# guac_v2.net
KiCad netlist of a schematic drawn in EAGLE
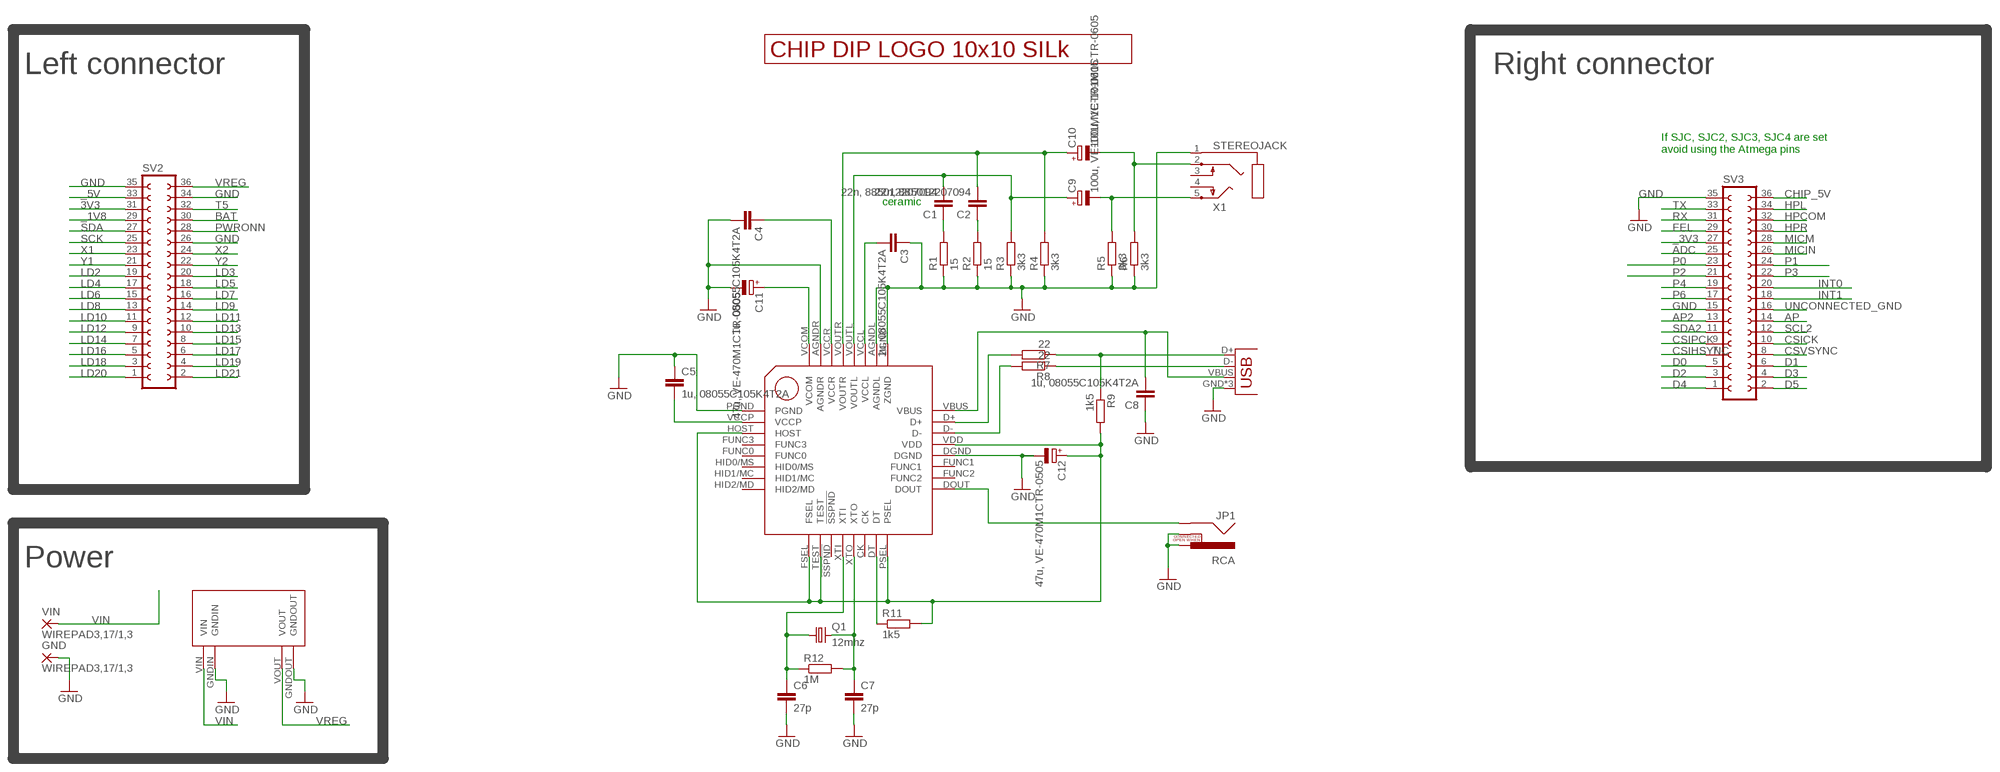
[diagram p0: schematic, sheet 1]

(export (version "E")
  (design (tool "Eeschema 10.0.6"))
  (components
    (comp (ref "C1")
      (value "22n, 885012207094")
      (footprint "eagle-import:C0805")
      (libsource (lib "eagle-import") (part "C-EUC0805"))
    )
    (comp (ref "C2")
      (value "22n, 885012207094")
      (footprint "eagle-import:C0805")
      (libsource (lib "eagle-import") (part "C-EUC0805"))
    )
    (comp (ref "C3")
      (value "1u, 08055C105K4T2A")
      (footprint "eagle-import:C0805")
      (libsource (lib "eagle-import") (part "C-EUC0805"))
    )
    (comp (ref "C4")
      (value "1u, 08055C105K4T2A")
      (footprint "eagle-import:C0805")
      (libsource (lib "eagle-import") (part "C-EUC0805"))
    )
    (comp (ref "C5")
      (value "1u, 08055C105K4T2A")
      (footprint "eagle-import:C0805")
      (libsource (lib "eagle-import") (part "C-EUC0805"))
    )
    (comp (ref "C6")
      (value "27p")
      (footprint "eagle-import:C0805")
      (libsource (lib "eagle-import") (part "C-EUC0805"))
    )
    (comp (ref "C7")
      (value "27p")
      (footprint "eagle-import:C0805")
      (libsource (lib "eagle-import") (part "C-EUC0805"))
    )
    (comp (ref "C8")
      (value "1u, 08055C105K4T2A")
      (footprint "eagle-import:C0805")
      (libsource (lib "eagle-import") (part "C-EUC0805"))
    )
    (comp (ref "C9")
      (value "100u, VE-101M1CTR-0605")
      (footprint "eagle-import:140CLH-0810")
      (libsource (lib "eagle-import") (part "CPOL-EU140CLH-0810"))
    )
    (comp (ref "C10")
      (value "100u, VE-101M1CTR-0605")
      (footprint "eagle-import:140CLH-0810")
      (libsource (lib "eagle-import") (part "CPOL-EU140CLH-0810"))
    )
    (comp (ref "C11")
      (value "47u, VE-470M1CTR-0505")
      (footprint "eagle-import:140CLH-0810")
      (libsource (lib "eagle-import") (part "CPOL-EU140CLH-0810"))
    )
    (comp (ref "C12")
      (value "47u, VE-470M1CTR-0505")
      (footprint "eagle-import:140CLH-0810")
      (libsource (lib "eagle-import") (part "CPOL-EU140CLH-0810"))
    )
    (comp (ref "GND")
      (value "WIREPAD3,17/1,3")
      (footprint "eagle-import:3,17_1,3")
      (libsource (lib "eagle-import") (part "WIREPAD3,17/1,3"))
    )
    (comp (ref "JP1")
      (value "RCA")
      (footprint "eagle-import:RCA")
      (libsource (lib "eagle-import") (part "RCA"))
    )
    (comp (ref "Q1")
      (value "12mhz")
      (footprint "eagle-import:HC49UP")
      (libsource (lib "eagle-import") (part "CRYSTALHC49UP"))
    )
    (comp (ref "R1")
      (value "15")
      (footprint "eagle-import:M0805")
      (libsource (lib "eagle-import") (part "R-EU_M0805"))
    )
    (comp (ref "R2")
      (value "15")
      (footprint "eagle-import:M0805")
      (libsource (lib "eagle-import") (part "R-EU_M0805"))
    )
    (comp (ref "R3")
      (value "3k3")
      (footprint "eagle-import:M0805")
      (libsource (lib "eagle-import") (part "R-EU_M0805"))
    )
    (comp (ref "R4")
      (value "3k3")
      (footprint "eagle-import:M0805")
      (libsource (lib "eagle-import") (part "R-EU_M0805"))
    )
    (comp (ref "R5")
      (value "3k3")
      (footprint "eagle-import:M0805")
      (libsource (lib "eagle-import") (part "R-EU_M0805"))
    )
    (comp (ref "R6")
      (value "3k3")
      (footprint "eagle-import:M0805")
      (libsource (lib "eagle-import") (part "R-EU_M0805"))
    )
    (comp (ref "R7")
      (value "22")
      (footprint "eagle-import:M0805")
      (libsource (lib "eagle-import") (part "R-EU_M0805"))
    )
    (comp (ref "R8")
      (value "22")
      (footprint "eagle-import:M0805")
      (libsource (lib "eagle-import") (part "R-EU_M0805"))
    )
    (comp (ref "R9")
      (value "1k5")
      (footprint "eagle-import:M0805")
      (libsource (lib "eagle-import") (part "R-EU_M0805"))
    )
    (comp (ref "R11")
      (value "1k5")
      (footprint "eagle-import:M0805")
      (libsource (lib "eagle-import") (part "R-EU_M0805"))
    )
    (comp (ref "R12")
      (value "1M")
      (footprint "eagle-import:M0805")
      (libsource (lib "eagle-import") (part "R-EU_M0805"))
    )
    (comp (ref "SV2")
      (value "FE18-2")
      (footprint "eagle-import:FE18-2")
      (libsource (lib "eagle-import") (part "FE18-2"))
    )
    (comp (ref "SV3")
      (value "FE18-2")
      (footprint "eagle-import:FE18-2")
      (libsource (lib "eagle-import") (part "FE18-2"))
    )
    (comp (ref "U$1")
      (value "PCM2706")
      (footprint "eagle-import:TQFP32-08")
      (libsource (lib "eagle-import") (part "PCM2706"))
    )
    (comp (ref "U$3")
      (value "LOGO_10X10_SILK")
      (footprint "eagle-import:LOGO_10X10_SILK")
      (libsource (lib "eagle-import") (part "LOGO_10X10_SILK"))
    )
    (comp (ref "U$9")
      (value "MP1584EN_FRAMELESS")
      (footprint "eagle-import:MP1584EN_FRAMELESS")
      (libsource (lib "eagle-import") (part "MP1584EN_FRAMELESS"))
    )
    (comp (ref "USB")
      (value "USBUSB-MICROB-SMT-DIP")
      (footprint "eagle-import:USB-MICROB-SMT-DIP")
      (libsource (lib "eagle-import") (part "USBUSB-MICROB-SMT-DIP"))
    )
    (comp (ref "VIN")
      (value "WIREPAD3,17/1,3")
      (footprint "eagle-import:3,17_1,3")
      (libsource (lib "eagle-import") (part "WIREPAD3,17/1,3"))
    )
    (comp (ref "X1")
      (value "STEREOJACK")
      (footprint "eagle-import:STX3100")
      (libsource (lib "eagle-import") (part "STEREOJACK"))
    )
  )
  (nets
    (net (code "1") (name "/3V3") (class "Default")
      (node (ref "SV2") (pin "31") (pinfunction "31_31") (pintype "passive"))
    )
    (net (code "2") (name "/ADC") (class "Default")
      (node (ref "SV3") (pin "25") (pinfunction "25_25") (pintype "passive"))
    )
    (net (code "3") (name "/AP") (class "Default")
      (node (ref "SV3") (pin "14") (pinfunction "14_14") (pintype "passive"))
    )
    (net (code "4") (name "/AP2") (class "Default")
      (node (ref "SV3") (pin "13") (pinfunction "13_13") (pintype "passive"))
    )
    (net (code "5") (name "/BAT") (class "Default")
      (node (ref "SV2") (pin "30") (pinfunction "30_30") (pintype "passive"))
    )
    (net (code "6") (name "/CHIP_5V") (class "Default")
      (node (ref "SV3") (pin "36") (pinfunction "36_36") (pintype "passive"))
    )
    (net (code "7") (name "/CSICK") (class "Default")
      (node (ref "SV3") (pin "10") (pinfunction "10_10") (pintype "passive"))
    )
    (net (code "8") (name "/CSIHSYNC") (class "Default")
      (node (ref "SV3") (pin "7") (pinfunction "7_7") (pintype "passive"))
    )
    (net (code "9") (name "/CSIPCK") (class "Default")
      (node (ref "SV3") (pin "9") (pinfunction "9_9") (pintype "passive"))
    )
    (net (code "10") (name "/CSVSYNC") (class "Default")
      (node (ref "SV3") (pin "8") (pinfunction "8_8") (pintype "passive"))
    )
    (net (code "11") (name "/D0") (class "Default")
      (node (ref "SV3") (pin "5") (pinfunction "5_5") (pintype "passive"))
    )
    (net (code "12") (name "/D1") (class "Default")
      (node (ref "SV3") (pin "6") (pinfunction "6_6") (pintype "passive"))
    )
    (net (code "13") (name "/D2") (class "Default")
      (node (ref "SV3") (pin "3") (pinfunction "3_3") (pintype "passive"))
    )
    (net (code "14") (name "/D3") (class "Default")
      (node (ref "SV3") (pin "4") (pinfunction "4_4") (pintype "passive"))
    )
    (net (code "15") (name "/D4") (class "Default")
      (node (ref "SV3") (pin "1") (pinfunction "1_1") (pintype "passive"))
    )
    (net (code "16") (name "/D5") (class "Default")
      (node (ref "SV3") (pin "2") (pinfunction "2_2") (pintype "passive"))
    )
    (net (code "17") (name "/FEL") (class "Default")
      (node (ref "SV3") (pin "29") (pinfunction "29_29") (pintype "passive"))
    )
    (net (code "18") (name "/HPCOM") (class "Default")
      (node (ref "SV3") (pin "32") (pinfunction "32_32") (pintype "passive"))
    )
    (net (code "19") (name "/HPL") (class "Default")
      (node (ref "SV3") (pin "34") (pinfunction "34_34") (pintype "passive"))
    )
    (net (code "20") (name "/HPR") (class "Default")
      (node (ref "SV3") (pin "30") (pinfunction "30_30") (pintype "passive"))
    )
    (net (code "21") (name "/INT0") (class "Default")
      (node (ref "SV3") (pin "20") (pinfunction "20_20") (pintype "passive"))
    )
    (net (code "22") (name "/INT1") (class "Default")
      (node (ref "SV3") (pin "18") (pinfunction "18_18") (pintype "passive"))
    )
    (net (code "23") (name "/LD2") (class "Default")
      (node (ref "SV2") (pin "19") (pinfunction "19_19") (pintype "passive"))
    )
    (net (code "24") (name "/LD3") (class "Default")
      (node (ref "SV2") (pin "20") (pinfunction "20_20") (pintype "passive"))
    )
    (net (code "25") (name "/LD4") (class "Default")
      (node (ref "SV2") (pin "17") (pinfunction "17_17") (pintype "passive"))
    )
    (net (code "26") (name "/LD5") (class "Default")
      (node (ref "SV2") (pin "18") (pinfunction "18_18") (pintype "passive"))
    )
    (net (code "27") (name "/LD6") (class "Default")
      (node (ref "SV2") (pin "15") (pinfunction "15_15") (pintype "passive"))
    )
    (net (code "28") (name "/LD7") (class "Default")
      (node (ref "SV2") (pin "16") (pinfunction "16_16") (pintype "passive"))
    )
    (net (code "29") (name "/LD8") (class "Default")
      (node (ref "SV2") (pin "13") (pinfunction "13_13") (pintype "passive"))
    )
    (net (code "30") (name "/LD9") (class "Default")
      (node (ref "SV2") (pin "14") (pinfunction "14_14") (pintype "passive"))
    )
    (net (code "31") (name "/LD10") (class "Default")
      (node (ref "SV2") (pin "11") (pinfunction "11_11") (pintype "passive"))
    )
    (net (code "32") (name "/LD11") (class "Default")
      (node (ref "SV2") (pin "12") (pinfunction "12_12") (pintype "passive"))
    )
    (net (code "33") (name "/LD12") (class "Default")
      (node (ref "SV2") (pin "9") (pinfunction "9_9") (pintype "passive"))
    )
    (net (code "34") (name "/LD13") (class "Default")
      (node (ref "SV2") (pin "10") (pinfunction "10_10") (pintype "passive"))
    )
    (net (code "35") (name "/LD14") (class "Default")
      (node (ref "SV2") (pin "7") (pinfunction "7_7") (pintype "passive"))
    )
    (net (code "36") (name "/LD15") (class "Default")
      (node (ref "SV2") (pin "8") (pinfunction "8_8") (pintype "passive"))
    )
    (net (code "37") (name "/LD16") (class "Default")
      (node (ref "SV2") (pin "5") (pinfunction "5_5") (pintype "passive"))
    )
    (net (code "38") (name "/LD17") (class "Default")
      (node (ref "SV2") (pin "6") (pinfunction "6_6") (pintype "passive"))
    )
    (net (code "39") (name "/LD18") (class "Default")
      (node (ref "SV2") (pin "3") (pinfunction "3_3") (pintype "passive"))
    )
    (net (code "40") (name "/LD19") (class "Default")
      (node (ref "SV2") (pin "4") (pinfunction "4_4") (pintype "passive"))
    )
    (net (code "41") (name "/LD20") (class "Default")
      (node (ref "SV2") (pin "1") (pinfunction "1_1") (pintype "passive"))
    )
    (net (code "42") (name "/LD21") (class "Default")
      (node (ref "SV2") (pin "2") (pinfunction "2_2") (pintype "passive"))
    )
    (net (code "43") (name "/MICIN") (class "Default")
      (node (ref "SV3") (pin "26") (pinfunction "26_26") (pintype "passive"))
    )
    (net (code "44") (name "/MICM") (class "Default")
      (node (ref "SV3") (pin "28") (pinfunction "28_28") (pintype "passive"))
    )
    (net (code "45") (name "/P0") (class "Default")
      (node (ref "SV3") (pin "23") (pinfunction "23_23") (pintype "passive"))
    )
    (net (code "46") (name "/P1") (class "Default")
      (node (ref "SV3") (pin "24") (pinfunction "24_24") (pintype "passive"))
    )
    (net (code "47") (name "/P2") (class "Default")
      (node (ref "SV3") (pin "21") (pinfunction "21_21") (pintype "passive"))
    )
    (net (code "48") (name "/P3") (class "Default")
      (node (ref "SV3") (pin "22") (pinfunction "22_22") (pintype "passive"))
    )
    (net (code "49") (name "/P4") (class "Default")
      (node (ref "SV3") (pin "19") (pinfunction "19_19") (pintype "passive"))
    )
    (net (code "50") (name "/P6") (class "Default")
      (node (ref "SV3") (pin "17") (pinfunction "17_17") (pintype "passive"))
    )
    (net (code "51") (name "/PWRONN") (class "Default")
      (node (ref "SV2") (pin "28") (pinfunction "28_28") (pintype "passive"))
    )
    (net (code "52") (name "/RX") (class "Default")
      (node (ref "SV3") (pin "31") (pinfunction "31_31") (pintype "passive"))
    )
    (net (code "53") (name "/SCK") (class "Default")
      (node (ref "SV2") (pin "25") (pinfunction "25_25") (pintype "passive"))
    )
    (net (code "54") (name "/SCL2") (class "Default")
      (node (ref "SV3") (pin "12") (pinfunction "12_12") (pintype "passive"))
    )
    (net (code "55") (name "/SDA") (class "Default")
      (node (ref "SV2") (pin "27") (pinfunction "27_27") (pintype "passive"))
    )
    (net (code "56") (name "/SDA2") (class "Default")
      (node (ref "SV3") (pin "11") (pinfunction "11_11") (pintype "passive"))
    )
    (net (code "57") (name "/T5") (class "Default")
      (node (ref "SV2") (pin "32") (pinfunction "32_32") (pintype "passive"))
    )
    (net (code "58") (name "/TX") (class "Default")
      (node (ref "SV3") (pin "33") (pinfunction "33_33") (pintype "passive"))
    )
    (net (code "59") (name "/UNCONNECTED_GND") (class "Default")
      (node (ref "SV3") (pin "16") (pinfunction "16_16") (pintype "passive"))
    )
    (net (code "60") (name "/VIN") (class "Default")
      (node (ref "U$9") (pin "VIN") (pinfunction "VIN_VIN") (pintype "power_in"))
      (node (ref "VIN") (pin "1") (pinfunction "P_1") (pintype "passive"))
    )
    (net (code "61") (name "/VREG") (class "Default")
      (node (ref "SV2") (pin "36") (pinfunction "36_36") (pintype "passive"))
      (node (ref "U$9") (pin "VOUT") (pinfunction "VOUT_VOUT") (pintype "power_in"))
    )
    (net (code "62") (name "/X1") (class "Default")
      (node (ref "SV2") (pin "23") (pinfunction "23_23") (pintype "passive"))
    )
    (net (code "63") (name "/X2") (class "Default")
      (node (ref "SV2") (pin "24") (pinfunction "24_24") (pintype "passive"))
    )
    (net (code "64") (name "/Y1") (class "Default")
      (node (ref "SV2") (pin "21") (pinfunction "21_21") (pintype "passive"))
    )
    (net (code "65") (name "/Y2") (class "Default")
      (node (ref "SV2") (pin "22") (pinfunction "22_22") (pintype "passive"))
    )
    (net (code "66") (name "/_1V8") (class "Default")
      (node (ref "SV2") (pin "29") (pinfunction "29_29") (pintype "passive"))
    )
    (net (code "67") (name "/_3V3") (class "Default")
      (node (ref "SV3") (pin "27") (pinfunction "27_27") (pintype "passive"))
    )
    (net (code "68") (name "/_5V") (class "Default")
      (node (ref "SV2") (pin "33") (pinfunction "33_33") (pintype "passive"))
    )
    (net (code "69") (name "GND") (class "Default")
      (node (ref "C11") (pin "-") (pinfunction "-_-") (pintype "passive"))
      (node (ref "C12") (pin "-") (pinfunction "-_-") (pintype "passive"))
      (node (ref "C3") (pin "1") (pinfunction "1_1") (pintype "passive"))
      (node (ref "C4") (pin "2") (pinfunction "2_2") (pintype "passive"))
      (node (ref "C5") (pin "1") (pinfunction "1_1") (pintype "passive"))
      (node (ref "C6") (pin "2") (pinfunction "2_2") (pintype "passive"))
      (node (ref "C7") (pin "2") (pinfunction "2_2") (pintype "passive"))
      (node (ref "C8") (pin "1") (pinfunction "1_1") (pintype "passive"))
      (node (ref "GND") (pin "1") (pinfunction "P_1") (pintype "passive"))
      (node (ref "JP1") (pin "PIN") (pinfunction "PIN_PIN") (pintype "bidirectional"))
      (node (ref "JP1") (pin "SWITCH") (pinfunction "SWITCH_SWITCH") (pintype "bidirectional"))
      (node (ref "R1") (pin "1") (pinfunction "1_1") (pintype "passive"))
      (node (ref "R2") (pin "1") (pinfunction "1_1") (pintype "passive"))
      (node (ref "R3") (pin "1") (pinfunction "1_1") (pintype "passive"))
      (node (ref "R4") (pin "1") (pinfunction "1_1") (pintype "passive"))
      (node (ref "R5") (pin "1") (pinfunction "1_1") (pintype "passive"))
      (node (ref "R6") (pin "1") (pinfunction "1_1") (pintype "passive"))
      (node (ref "SV2") (pin "26") (pinfunction "26_26") (pintype "passive"))
      (node (ref "SV2") (pin "34") (pinfunction "34_34") (pintype "passive"))
      (node (ref "SV2") (pin "35") (pinfunction "35_35") (pintype "passive"))
      (node (ref "SV3") (pin "15") (pinfunction "15_15") (pintype "passive"))
      (node (ref "SV3") (pin "35") (pinfunction "35_35") (pintype "passive"))
      (node (ref "U$1") (pin "AGNDL") (pinfunction "AGNDL_AGNDL") (pintype "power_in"))
      (node (ref "U$1") (pin "AGNDR") (pinfunction "AGNDR_AGNDR") (pintype "power_in"))
      (node (ref "U$1") (pin "DGND") (pinfunction "DGND_DGND") (pintype "power_in"))
      (node (ref "U$1") (pin "PGND") (pinfunction "PGND_PGND") (pintype "power_in"))
      (node (ref "U$1") (pin "ZGND") (pinfunction "ZGND_ZGND") (pintype "power_in"))
      (node (ref "U$9") (pin "GNDIN") (pinfunction "GNDIN_GNDIN") (pintype "power_in"))
      (node (ref "U$9") (pin "GNDOUT") (pinfunction "GNDOUT_GNDOUT") (pintype "power_in"))
      (node (ref "USB") (pin "GND") (pinfunction "GND_GND") (pintype "bidirectional"))
      (node (ref "USB") (pin "MT1") (pinfunction "GND_MT1") (pintype "bidirectional"))
      (node (ref "USB") (pin "MT2") (pinfunction "GND_MT2") (pintype "bidirectional"))
      (node (ref "X1") (pin "1") (pinfunction "1_1") (pintype "passive"))
    )
    (net (code "70") (name "Net-(C1-Pad1)") (class "Default")
      (node (ref "C1") (pin "1") (pinfunction "1_1") (pintype "passive"))
      (node (ref "R1") (pin "2") (pinfunction "2_2") (pintype "passive"))
    )
    (net (code "71") (name "Net-(C1-Pad2)") (class "Default")
      (node (ref "C1") (pin "2") (pinfunction "2_2") (pintype "passive"))
      (node (ref "C9") (pin "+") (pinfunction "+_+") (pintype "passive"))
      (node (ref "R3") (pin "2") (pinfunction "2_2") (pintype "passive"))
      (node (ref "U$1") (pin "VOUTL") (pinfunction "VOUTL_VOUTL") (pintype "output"))
    )
    (net (code "72") (name "Net-(C2-Pad1)") (class "Default")
      (node (ref "C2") (pin "1") (pinfunction "1_1") (pintype "passive"))
      (node (ref "R2") (pin "2") (pinfunction "2_2") (pintype "passive"))
    )
    (net (code "73") (name "Net-(C3-Pad2)") (class "Default")
      (node (ref "C3") (pin "2") (pinfunction "2_2") (pintype "passive"))
      (node (ref "U$1") (pin "VCCL") (pinfunction "VCCL_VCCL") (pintype "power_in"))
    )
    (net (code "74") (name "Net-(C4-Pad1)") (class "Default")
      (node (ref "C4") (pin "1") (pinfunction "1_1") (pintype "passive"))
      (node (ref "U$1") (pin "VCCR") (pinfunction "VCCR_VCCR") (pintype "power_in"))
    )
    (net (code "75") (name "Net-(C5-Pad2)") (class "Default")
      (node (ref "C5") (pin "2") (pinfunction "2_2") (pintype "passive"))
      (node (ref "U$1") (pin "VCCP") (pinfunction "VCCP_VCCP") (pintype "power_in"))
    )
    (net (code "76") (name "Net-(C6-Pad1)") (class "Default")
      (node (ref "C6") (pin "1") (pinfunction "1_1") (pintype "passive"))
      (node (ref "Q1") (pin "1") (pinfunction "1_1") (pintype "passive"))
      (node (ref "R12") (pin "1") (pinfunction "1_1") (pintype "passive"))
      (node (ref "U$1") (pin "XTI") (pinfunction "XTI_XTI") (pintype "bidirectional"))
    )
    (net (code "77") (name "Net-(C7-Pad1)") (class "Default")
      (node (ref "C7") (pin "1") (pinfunction "1_1") (pintype "passive"))
      (node (ref "Q1") (pin "2") (pinfunction "2_2") (pintype "passive"))
      (node (ref "R12") (pin "2") (pinfunction "2_2") (pintype "passive"))
      (node (ref "U$1") (pin "XTO") (pinfunction "XTO_XTO") (pintype "bidirectional"))
    )
    (net (code "78") (name "Net-(C8-Pad2)") (class "Default")
      (node (ref "C8") (pin "2") (pinfunction "2_2") (pintype "passive"))
      (node (ref "U$1") (pin "VBUS") (pinfunction "VBUS_VBUS") (pintype "power_in"))
      (node (ref "USB") (pin "VBUS") (pinfunction "VBUS_VBUS") (pintype "bidirectional"))
    )
    (net (code "79") (name "Net-(C9-Pad-)") (class "Default")
      (node (ref "C9") (pin "-") (pinfunction "-_-") (pintype "passive"))
      (node (ref "R5") (pin "2") (pinfunction "2_2") (pintype "passive"))
      (node (ref "X1") (pin "5") (pinfunction "5_5") (pintype "passive"))
    )
    (net (code "80") (name "Net-(C10-Pad+)") (class "Default")
      (node (ref "C10") (pin "+") (pinfunction "+_+") (pintype "passive"))
      (node (ref "C2") (pin "2") (pinfunction "2_2") (pintype "passive"))
      (node (ref "R4") (pin "2") (pinfunction "2_2") (pintype "passive"))
      (node (ref "U$1") (pin "VOUTR") (pinfunction "VOUTR_VOUTR") (pintype "output"))
    )
    (net (code "81") (name "Net-(C10-Pad-)") (class "Default")
      (node (ref "C10") (pin "-") (pinfunction "-_-") (pintype "passive"))
      (node (ref "R6") (pin "2") (pinfunction "2_2") (pintype "passive"))
      (node (ref "X1") (pin "2") (pinfunction "2_2") (pintype "passive"))
    )
    (net (code "82") (name "Net-(C11-Pad+)") (class "Default")
      (node (ref "C11") (pin "+") (pinfunction "+_+") (pintype "passive"))
      (node (ref "U$1") (pin "VCOM") (pinfunction "VCOM_VCOM") (pintype "power_in"))
    )
    (net (code "83") (name "Net-(C12-Pad+)") (class "Default")
      (node (ref "C12") (pin "+") (pinfunction "+_+") (pintype "passive"))
      (node (ref "R11") (pin "2") (pinfunction "2_2") (pintype "passive"))
      (node (ref "R9") (pin "2") (pinfunction "2_2") (pintype "passive"))
      (node (ref "U$1") (pin "FSEL") (pinfunction "FSEL_FSEL") (pintype "bidirectional"))
      (node (ref "U$1") (pin "HOST") (pinfunction "HOST_HOST") (pintype "power_in"))
      (node (ref "U$1") (pin "PSEL") (pinfunction "PSEL_PSEL") (pintype "bidirectional"))
      (node (ref "U$1") (pin "TEST") (pinfunction "TEST_TEST") (pintype "bidirectional"))
      (node (ref "U$1") (pin "VDD") (pinfunction "VDD_VDD") (pintype "power_in"))
    )
    (net (code "84") (name "Net-(JP1-PadSHELL)") (class "Default")
      (node (ref "JP1") (pin "SHELL") (pinfunction "SHELL_SHELL") (pintype "bidirectional"))
      (node (ref "U$1") (pin "DOUT") (pinfunction "DOUT_DOUT") (pintype "bidirectional"))
    )
    (net (code "85") (name "Net-(R7-Pad1)") (class "Default")
      (node (ref "R7") (pin "1") (pinfunction "1_1") (pintype "passive"))
      (node (ref "R9") (pin "1") (pinfunction "1_1") (pintype "passive"))
      (node (ref "USB") (pin "D+") (pinfunction "D+_D+") (pintype "bidirectional"))
    )
    (net (code "86") (name "Net-(R7-Pad2)") (class "Default")
      (node (ref "R7") (pin "2") (pinfunction "2_2") (pintype "passive"))
      (node (ref "U$1") (pin "D+") (pinfunction "D+_D+") (pintype "bidirectional"))
    )
    (net (code "87") (name "Net-(R8-Pad1)") (class "Default")
      (node (ref "R8") (pin "1") (pinfunction "1_1") (pintype "passive"))
      (node (ref "USB") (pin "D-") (pinfunction "D-_D-") (pintype "bidirectional"))
    )
    (net (code "88") (name "Net-(R8-Pad2)") (class "Default")
      (node (ref "R8") (pin "2") (pinfunction "2_2") (pintype "passive"))
      (node (ref "U$1") (pin "D-") (pinfunction "D-_D-") (pintype "bidirectional"))
    )
    (net (code "89") (name "Net-(R11-Pad1)") (class "Default")
      (node (ref "R11") (pin "1") (pinfunction "1_1") (pintype "passive"))
      (node (ref "U$1") (pin "DT") (pinfunction "DT_DT") (pintype "bidirectional"))
    )
    (net (code "90") (name "unconnected-(U$1-PadCK)") (class "Default")
      (node (ref "U$1") (pin "CK") (pinfunction "CK_CK") (pintype "bidirectional"))
    )
    (net (code "91") (name "unconnected-(U$1-PadFUNC0)") (class "Default")
      (node (ref "U$1") (pin "FUNC0") (pinfunction "FUNC0_FUNC0") (pintype "bidirectional"))
    )
    (net (code "92") (name "unconnected-(U$1-PadFUNC1)") (class "Default")
      (node (ref "U$1") (pin "FUNC1") (pinfunction "FUNC1_FUNC1") (pintype "bidirectional"))
    )
    (net (code "93") (name "unconnected-(U$1-PadFUNC2)") (class "Default")
      (node (ref "U$1") (pin "FUNC2") (pinfunction "FUNC2_FUNC2") (pintype "bidirectional"))
    )
    (net (code "94") (name "unconnected-(U$1-PadFUNC3)") (class "Default")
      (node (ref "U$1") (pin "FUNC3") (pinfunction "FUNC3_FUNC3") (pintype "bidirectional"))
    )
    (net (code "95") (name "unconnected-(U$1-PadHID0{slash}MS)") (class "Default")
      (node (ref "U$1") (pin "HID0/MS") (pinfunction "HID0/MS_HID0/MS") (pintype "bidirectional"))
    )
    (net (code "96") (name "unconnected-(U$1-PadHID1{slash}MC)") (class "Default")
      (node (ref "U$1") (pin "HID1/MC") (pinfunction "HID1/MC_HID1/MC") (pintype "bidirectional"))
    )
    (net (code "97") (name "unconnected-(U$1-PadHID2{slash}MD)") (class "Default")
      (node (ref "U$1") (pin "HID2/MD") (pinfunction "HID2/MD_HID2/MD") (pintype "bidirectional"))
    )
    (net (code "98") (name "unconnected-(U$1-~{SSPND}-Pad!SSPND)") (class "Default")
      (node (ref "U$1") (pin "!SSPND") (pinfunction "~{SSPND}_!SSPND") (pintype "bidirectional"))
    )
    (net (code "99") (name "unconnected-(X1-Pad3)") (class "Default")
      (node (ref "X1") (pin "3") (pinfunction "3_3") (pintype "passive"))
    )
    (net (code "100") (name "unconnected-(X1-Pad4)") (class "Default")
      (node (ref "X1") (pin "4") (pinfunction "4_4") (pintype "passive"))
    )
  )
)
